# Sheet1.net
KiCad netlist of a schematic drawn in Altium Designer
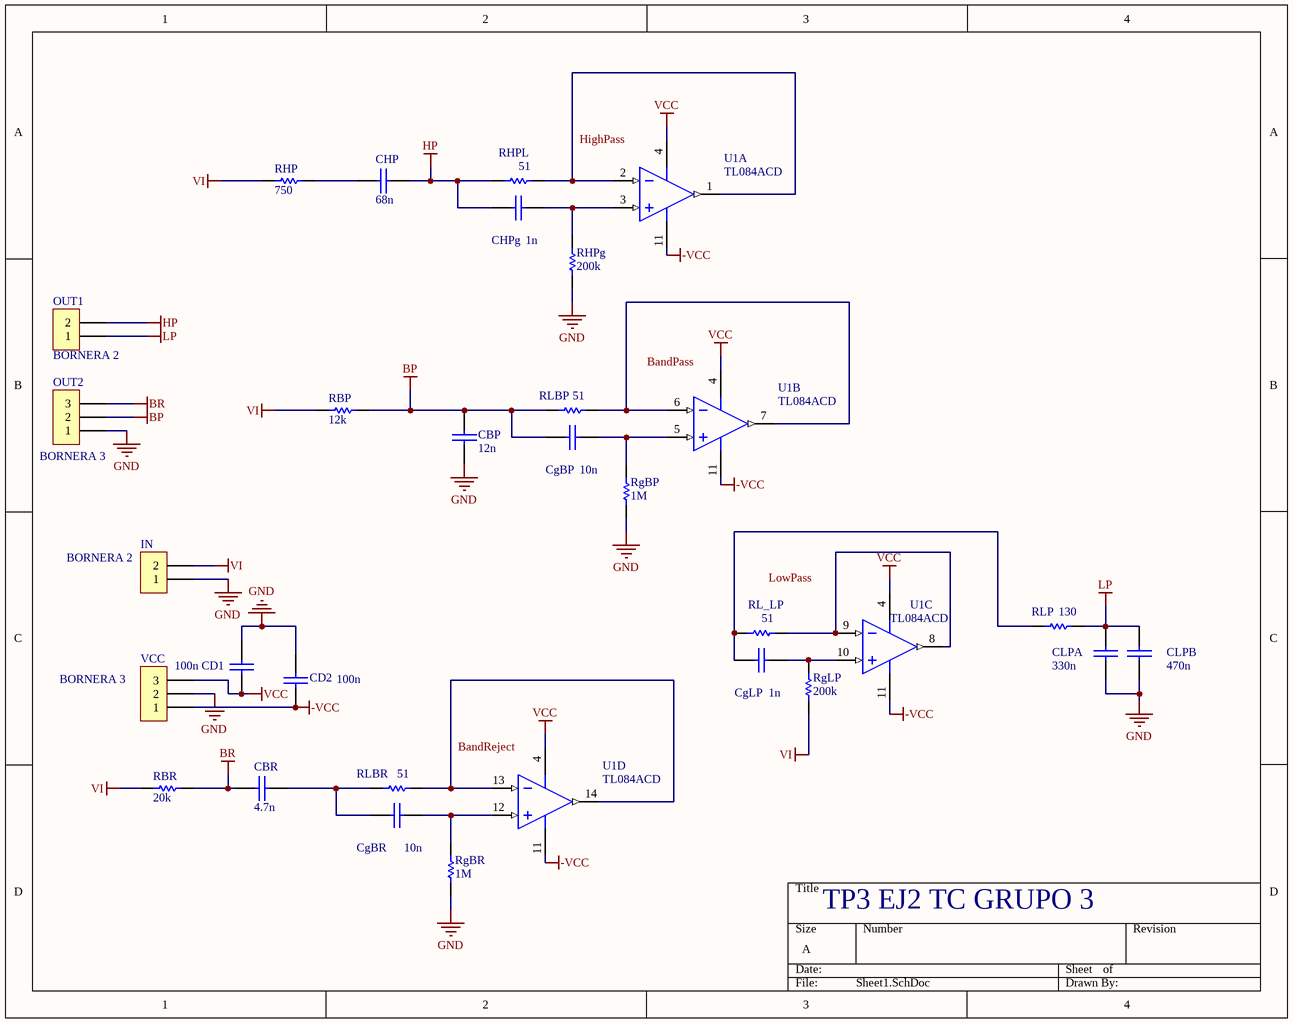
[diagram p0: Sheet1.SchDoc]

(export (version "E")
  (design (tool "Eeschema 10.0.6"))
  (components
    (comp (ref "CBP") (value "12n") (footprint "0805") (libsource (lib "LIBEBAL") (part "CAP")))
    (comp (ref "CBR") (value "4.7n") (footprint "0805") (libsource (lib "LIBEBAL") (part "CAP")))
    (comp (ref "CD1") (value "100n") (footprint "CAP100") (libsource (lib "LIBEBAL") (part "CAP")))
    (comp (ref "CD2") (value "100n") (footprint "CAP100") (libsource (lib "LIBEBAL") (part "CAP")))
    (comp (ref "CgBP") (value "10n") (footprint "0805") (libsource (lib "LIBEBAL") (part "CAP")))
    (comp (ref "CgBR") (value "10n") (footprint "0805") (libsource (lib "LIBEBAL") (part "CAP")))
    (comp (ref "CgLP") (value "1n") (footprint "0805") (libsource (lib "LIBEBAL") (part "CAP")))
    (comp (ref "CHP") (value "68n") (footprint "0805") (libsource (lib "LIBEBAL") (part "CAP")))
    (comp (ref "CHPg") (value "1n") (footprint "0805") (libsource (lib "LIBEBAL") (part "CAP")))
    (comp (ref "CLPA") (value "330n") (footprint "0805") (libsource (lib "LIBEBAL") (part "CAP")))
    (comp (ref "CLPB") (value "470n") (footprint "0805") (libsource (lib "LIBEBAL") (part "CAP")))
    (comp (ref "IN")
      (value "BORNERA 2")
      (footprint "BORNERA2")
      (libsource (lib "LIB PIO IX") (part "BORNERA 2"))
    )
    (comp (ref "OUT1")
      (value "BORNERA 2")
      (footprint "BORNERA2")
      (libsource (lib "LIB PIO IX") (part "BORNERA 2"))
    )
    (comp (ref "OUT2")
      (value "BORNERA 3")
      (footprint "BORNERA3")
      (libsource (lib "LIB PIO IX") (part "BORNERA 3"))
    )
    (comp (ref "RBP") (value "12k") (footprint "0805") (libsource (lib "LIBEBAL") (part "RES")))
    (comp (ref "RBR") (value "20k") (footprint "0805") (libsource (lib "LIBEBAL") (part "RES")))
    (comp (ref "RgBP") (value "1M") (footprint "0805") (libsource (lib "LIBEBAL") (part "RES")))
    (comp (ref "RgBR") (value "1M") (footprint "0805") (libsource (lib "LIBEBAL") (part "RES")))
    (comp (ref "RgLP") (value "200k") (footprint "0805") (libsource (lib "LIBEBAL") (part "RES")))
    (comp (ref "RHP") (value "750") (footprint "0805") (libsource (lib "LIBEBAL") (part "RES")))
    (comp (ref "RHPg") (value "200k") (footprint "0805") (libsource (lib "LIBEBAL") (part "RES")))
    (comp (ref "RHPL") (value "51") (footprint "0805") (libsource (lib "LIBEBAL") (part "RES")))
    (comp (ref "RLBP") (value "51") (footprint "0805") (libsource (lib "LIBEBAL") (part "RES")))
    (comp (ref "RLBR") (value "51") (footprint "0805") (libsource (lib "LIBEBAL") (part "RES")))
    (comp (ref "RLP") (value "130") (footprint "0805") (libsource (lib "LIBEBAL") (part "RES")))
    (comp (ref "RL_LP") (value "51") (footprint "0805") (libsource (lib "LIBEBAL") (part "RES")))
    (comp (ref "U1")
      (value "TL084ACD")
      (footprint "DIP14")
      (fields (field (name "MANUFACTURER") "Texas Instruments"))
      (libsource (lib "TI Amplifiers and Linear Operational Amplifier General Purpose") (part "TL084ACD"))
    )
    (comp (ref "VCC")
      (value "BORNERA 3")
      (footprint "BORNERA3")
      (libsource (lib "LIB PIO IX") (part "BORNERA 3"))
    )
  )
  (nets
    (net (code "1") (name "-VCC") (class "Default")
      (node (ref "CD2") (pin "1") (pinfunction "1_1") (pintype "passive"))
      (node (ref "U1") (pin "11") (pinfunction "VCC-_11") (pintype "power_in"))
      (node (ref "VCC") (pin "1") (pinfunction "1_1") (pintype "passive"))
    )
    (net (code "6") (name "BP") (class "Default")
      (node (ref "CBP") (pin "2") (pinfunction "2_2") (pintype "passive"))
      (node (ref "CgBP") (pin "1") (pinfunction "1_1") (pintype "passive"))
      (node (ref "OUT2") (pin "2") (pinfunction "2_2") (pintype "passive"))
      (node (ref "RBP") (pin "2") (pinfunction "2_2") (pintype "passive"))
      (node (ref "RLBP") (pin "1") (pinfunction "1_1") (pintype "passive"))
    )
    (net (code "7") (name "BR") (class "Default")
      (node (ref "CBR") (pin "1") (pinfunction "1_1") (pintype "passive"))
      (node (ref "OUT2") (pin "3") (pinfunction "3_3") (pintype "passive"))
      (node (ref "RBR") (pin "2") (pinfunction "2_2") (pintype "passive"))
    )
    (net (code "8") (name "GND") (class "Default")
      (node (ref "CBP") (pin "1") (pinfunction "1_1") (pintype "passive"))
      (node (ref "CD1") (pin "1") (pinfunction "1_1") (pintype "passive"))
      (node (ref "CD2") (pin "2") (pinfunction "2_2") (pintype "passive"))
      (node (ref "CLPA") (pin "1") (pinfunction "1_1") (pintype "passive"))
      (node (ref "CLPB") (pin "1") (pinfunction "1_1") (pintype "passive"))
      (node (ref "IN") (pin "1") (pinfunction "1_1") (pintype "passive"))
      (node (ref "OUT2") (pin "1") (pinfunction "1_1") (pintype "passive"))
      (node (ref "RHPg") (pin "1") (pinfunction "1_1") (pintype "passive"))
      (node (ref "RgBP") (pin "1") (pinfunction "1_1") (pintype "passive"))
      (node (ref "RgBR") (pin "1") (pinfunction "1_1") (pintype "passive"))
      (node (ref "VCC") (pin "2") (pinfunction "2_2") (pintype "passive"))
    )
    (net (code "9") (name "HP") (class "Default")
      (node (ref "CHP") (pin "2") (pinfunction "2_2") (pintype "passive"))
      (node (ref "CHPg") (pin "1") (pinfunction "1_1") (pintype "passive"))
      (node (ref "OUT1") (pin "2") (pinfunction "2_2") (pintype "passive"))
      (node (ref "RHPL") (pin "1") (pinfunction "1_1") (pintype "passive"))
    )
    (net (code "10") (name "LP") (class "Default")
      (node (ref "CLPA") (pin "2") (pinfunction "2_2") (pintype "passive"))
      (node (ref "CLPB") (pin "2") (pinfunction "2_2") (pintype "passive"))
      (node (ref "OUT1") (pin "1") (pinfunction "1_1") (pintype "passive"))
      (node (ref "RLP") (pin "2") (pinfunction "2_2") (pintype "passive"))
    )
    (net (code "11") (name "Net-(CBR-Pad2)") (class "Default")
      (node (ref "CBR") (pin "2") (pinfunction "2_2") (pintype "passive"))
      (node (ref "CgBR") (pin "1") (pinfunction "1_1") (pintype "passive"))
      (node (ref "RLBR") (pin "1") (pinfunction "1_1") (pintype "passive"))
    )
    (net (code "12") (name "Net-(CHP-Pad1)") (class "Default")
      (node (ref "CHP") (pin "1") (pinfunction "1_1") (pintype "passive"))
      (node (ref "RHP") (pin "2") (pinfunction "2_2") (pintype "passive"))
    )
    (net (code "13") (name "Net-(CgLP-Pad1)") (class "Default")
      (node (ref "CgLP") (pin "1") (pinfunction "1_1") (pintype "passive"))
      (node (ref "RLP") (pin "1") (pinfunction "1_1") (pintype "passive"))
      (node (ref "RL_LP") (pin "1") (pinfunction "1_1") (pintype "passive"))
    )
    (net (code "14") (name "Net-(U1A-IN1+)") (class "Default")
      (node (ref "CHPg") (pin "2") (pinfunction "2_2") (pintype "passive"))
      (node (ref "RHPg") (pin "2") (pinfunction "2_2") (pintype "passive"))
      (node (ref "U1") (pin "3") (pinfunction "IN1+_3") (pintype "input"))
    )
    (net (code "15") (name "Net-(U1A-IN1-)") (class "Default")
      (node (ref "RHPL") (pin "2") (pinfunction "2_2") (pintype "passive"))
      (node (ref "U1") (pin "1") (pinfunction "OUT1_1") (pintype "output"))
      (node (ref "U1") (pin "2") (pinfunction "IN1-_2") (pintype "input"))
    )
    (net (code "16") (name "Net-(U1B-IN2+)") (class "Default")
      (node (ref "CgBP") (pin "2") (pinfunction "2_2") (pintype "passive"))
      (node (ref "RgBP") (pin "2") (pinfunction "2_2") (pintype "passive"))
      (node (ref "U1") (pin "5") (pinfunction "IN2+_5") (pintype "input"))
    )
    (net (code "17") (name "Net-(U1B-IN2-)") (class "Default")
      (node (ref "RLBP") (pin "2") (pinfunction "2_2") (pintype "passive"))
      (node (ref "U1") (pin "6") (pinfunction "IN2-_6") (pintype "input"))
      (node (ref "U1") (pin "7") (pinfunction "OUT2_7") (pintype "output"))
    )
    (net (code "18") (name "Net-(U1C-IN3+)") (class "Default")
      (node (ref "CgLP") (pin "2") (pinfunction "2_2") (pintype "passive"))
      (node (ref "RgLP") (pin "2") (pinfunction "2_2") (pintype "passive"))
      (node (ref "U1") (pin "10") (pinfunction "IN3+_10") (pintype "input"))
    )
    (net (code "19") (name "Net-(U1C-IN3-)") (class "Default")
      (node (ref "RL_LP") (pin "2") (pinfunction "2_2") (pintype "passive"))
      (node (ref "U1") (pin "8") (pinfunction "OUT3_8") (pintype "output"))
      (node (ref "U1") (pin "9") (pinfunction "IN3-_9") (pintype "input"))
    )
    (net (code "20") (name "Net-(U1D-IN4+)") (class "Default")
      (node (ref "CgBR") (pin "2") (pinfunction "2_2") (pintype "passive"))
      (node (ref "RgBR") (pin "2") (pinfunction "2_2") (pintype "passive"))
      (node (ref "U1") (pin "12") (pinfunction "IN4+_12") (pintype "input"))
    )
    (net (code "21") (name "Net-(U1D-IN4-)") (class "Default")
      (node (ref "RLBR") (pin "2") (pinfunction "2_2") (pintype "passive"))
      (node (ref "U1") (pin "13") (pinfunction "IN4-_13") (pintype "input"))
      (node (ref "U1") (pin "14") (pinfunction "OUT4_14") (pintype "output"))
    )
    (net (code "22") (name "VCC") (class "Default")
      (node (ref "CD1") (pin "2") (pinfunction "2_2") (pintype "passive"))
      (node (ref "U1") (pin "4") (pinfunction "VCC+_4") (pintype "power_in"))
      (node (ref "VCC") (pin "3") (pinfunction "3_3") (pintype "passive"))
    )
    (net (code "23") (name "VI") (class "Default")
      (node (ref "IN") (pin "2") (pinfunction "2_2") (pintype "passive"))
      (node (ref "RBP") (pin "1") (pinfunction "1_1") (pintype "passive"))
      (node (ref "RBR") (pin "1") (pinfunction "1_1") (pintype "passive"))
      (node (ref "RHP") (pin "1") (pinfunction "1_1") (pintype "passive"))
      (node (ref "RgLP") (pin "1") (pinfunction "1_1") (pintype "passive"))
    )
  )
)
